# ESP32.net
KiCad netlist of a schematic drawn in Altium Designer
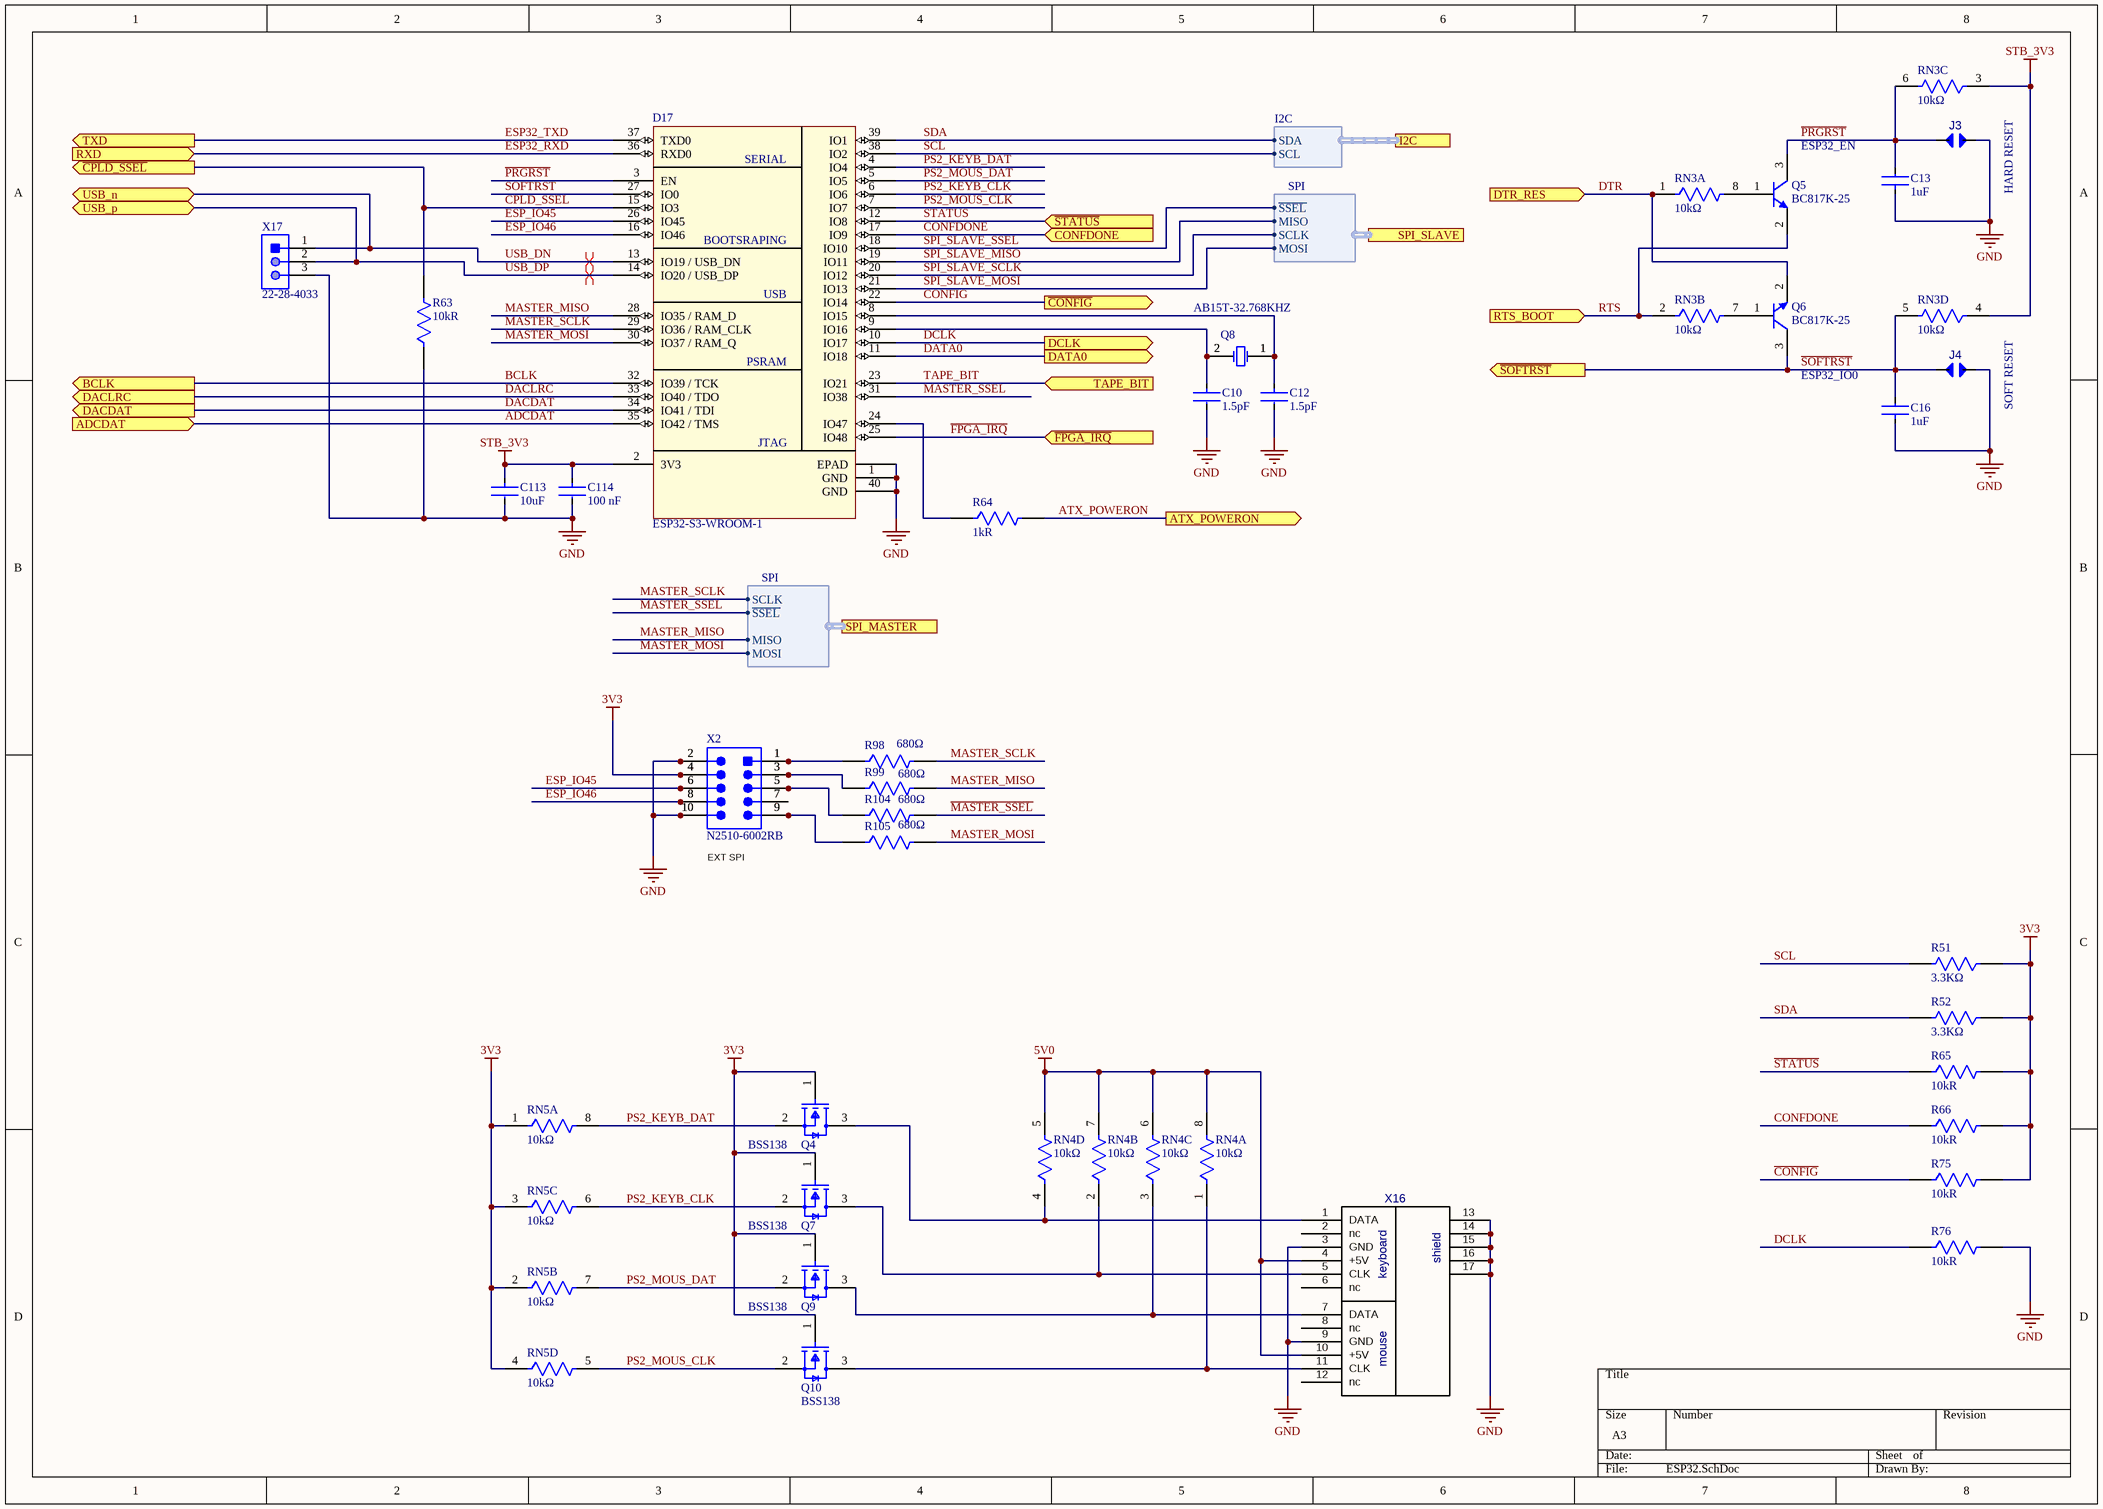
[diagram p0: ESP32.SchDoc]

(export (version "E")
  (design (tool "Eeschema 10.0.6"))
  (components
    (comp (ref "C10")
      (value "CL21C1R5CBANNNC")
      (footprint "FP-CL21-IPC_A")
      (description "CL21 Series 0805 1.5pF 50V ±0.25pF Tolerance C0G Multilayer Ceramic Chip Capacitor")
      (fields (field (name "CAPACITANCE") "1.5pF") (field (name "MANUFACTURER") "Samsung"))
      (libsource (lib "SchLib") (part "CMP-13271-001925-1"))
    )
    (comp (ref "C12")
      (value "CL21C1R5CBANNNC")
      (footprint "FP-CL21-IPC_A")
      (description "CL21 Series 0805 1.5pF 50V ±0.25pF Tolerance C0G Multilayer Ceramic Chip Capacitor")
      (fields (field (name "CAPACITANCE") "1.5pF") (field (name "MANUFACTURER") "Samsung"))
      (libsource (lib "SchLib") (part "CMP-13271-001925-1"))
    )
    (comp (ref "C13")
      (value "GCM21BR71E105KA56L")
      (footprint "FP-GCM21B-0_15-IPC_A")
      (description "Ceramic Capacitor for Automotive 1uF ±10% 25VDC X7R 0805 Embossed T/R")
      (fields (field (name "CAPACITANCE") "1uF") (field (name "MANUFACTURER") "Murata"))
      (libsource (lib "SchLib") (part "CMP-2007-03346-2"))
    )
    (comp (ref "C16")
      (value "GCM21BR71E105KA56L")
      (footprint "FP-GCM21B-0_15-IPC_A")
      (description "Ceramic Capacitor for Automotive 1uF ±10% 25VDC X7R 0805 Embossed T/R")
      (fields (field (name "CAPACITANCE") "1uF") (field (name "MANUFACTURER") "Murata"))
      (libsource (lib "SchLib") (part "CMP-2007-03346-2"))
    )
    (comp (ref "C113")
      (value "C0805C106K8PACTU")
      (footprint "FP-C0805C-DG-IPC_A")
      (description "CAP CER 10UF 10V X5R 0805")
      (fields (field (name "MANUFACTURER") "KEMET") (field (name "CAPACITANCE") "10uF"))
      (libsource (lib "SchLib") (part "CMP-2007-03243-2"))
    )
    (comp (ref "C114")
      (value "CC0805KRX7R9BB104")
      (footprint "FP-CC0805-0_85-IPC_A")
      (description "CAP CER 0.1UF 50V X7R 0805")
      (fields (field (name "MANUFACTURER") "Yageo") (field (name "CAPACITANCE") "100 nF"))
      (libsource (lib "SchLib") (part "CMP-2100-03606-3"))
    )
    (comp (ref "D17")
      (value "ESP32-S3-WROOM-1")
      (footprint "ESP32S3WROOM1")
      (libsource (lib "SchLib") (part "ESP32-S3-WROOM-1"))
    )
    (comp (ref "J3")
      (value "JUMPER")
      (footprint "JUMPER_JUMPER(Primary)")
      (description "HLT->~IP")
      (libsource (lib "SchLib") (part "JUMPER"))
    )
    (comp (ref "J4")
      (value "JUMPER")
      (footprint "JUMPER_JUMPER(Primary)")
      (description "HLT->~IP")
      (libsource (lib "SchLib") (part "JUMPER"))
    )
    (comp (ref "Q4")
      (value "BSS138")
      (footprint "FP-318-08-IPC_B")
      (description "MOSFET N-CH 50V 220MA SOT-23")
      (fields (field (name "MANUFACTURER") "ON Semiconductor / Fairchild"))
      (libsource (lib "SchLib") (part "CMP-07173-000101-1"))
    )
    (comp (ref "Q5")
      (value "BC817K-25")
      (footprint "INF-SOT23_N")
      (description "NPN Silicon AF Transistor, 45 V VCEO, 500 mA IC, SOT23, Reel, Green")
      (fields (field (name "MANUFACTURER") "Infineon"))
      (libsource (lib "SchLib") (part "CMP-1177-00027-1"))
    )
    (comp (ref "Q6")
      (value "BC817K-25")
      (footprint "INF-SOT23_N")
      (description "NPN Silicon AF Transistor, 45 V VCEO, 500 mA IC, SOT23, Reel, Green")
      (fields (field (name "MANUFACTURER") "Infineon"))
      (libsource (lib "SchLib") (part "CMP-1177-00027-1"))
    )
    (comp (ref "Q7")
      (value "BSS138")
      (footprint "FP-318-08-IPC_B")
      (description "MOSFET N-CH 50V 220MA SOT-23")
      (fields (field (name "MANUFACTURER") "ON Semiconductor / Fairchild"))
      (libsource (lib "SchLib") (part "CMP-07173-000101-1"))
    )
    (comp (ref "Q8")
      (value "AB15T-32.768KHZ")
      (footprint "ABRA-AB15T-2_V")
      (fields (field (name "MANUFACTURER") "Abracon"))
      (libsource (lib "SchLib") (part "CMP-1326-00001-1"))
    )
    (comp (ref "Q9")
      (value "BSS138")
      (footprint "FP-318-08-IPC_B")
      (description "MOSFET N-CH 50V 220MA SOT-23")
      (fields (field (name "MANUFACTURER") "ON Semiconductor / Fairchild"))
      (libsource (lib "SchLib") (part "CMP-07173-000101-1"))
    )
    (comp (ref "Q10")
      (value "BSS138")
      (footprint "FP-318-08-IPC_B")
      (description "MOSFET N-CH 50V 220MA SOT-23")
      (fields (field (name "MANUFACTURER") "ON Semiconductor / Fairchild"))
      (libsource (lib "SchLib") (part "CMP-07173-000101-1"))
    )
    (comp (ref "R51")
      (value "RT0805FRE073K3L")
      (footprint "FP-RT0805-IPC_A")
      (description "RES SMD 3.3K OHM 1% 1/8W 0805")
      (fields (field (name "MANUFACTURER") "Yageo") (field (name "RESISTANCE") "3.3KΩ"))
      (libsource (lib "SchLib") (part "CMP-03412-025935-1"))
    )
    (comp (ref "R52")
      (value "RT0805FRE073K3L")
      (footprint "FP-RT0805-IPC_A")
      (description "RES SMD 3.3K OHM 1% 1/8W 0805")
      (fields (field (name "MANUFACTURER") "Yageo") (field (name "RESISTANCE") "3.3KΩ"))
      (libsource (lib "SchLib") (part "CMP-03412-025935-1"))
    )
    (comp (ref "R63")
      (value "CR0805-JW-103ELF")
      (footprint "FP-CR0805-IPC_A")
      (description "Thick Film Chip Resistors 0805 10kΩ 0.125W 5% 200ppm/°C")
      (fields (field (name "RESISTANCE") "10kR") (field (name "MANUFACTURER") "Bourns"))
      (libsource (lib "SchLib") (part "CMP-07231-003873-1"))
    )
    (comp (ref "R64")
      (value "MCR10ERTJ102")
      (footprint "FP-MCR10-IPC_A")
      (description "Thick Film Chip Resistor, 0805, 1kΩ, 5%, 200ppm/°C, 0.125W, 150V")
      (fields (field (name "RESISTANCE") "1kR") (field (name "MANUFACTURER") "Rohm"))
      (libsource (lib "SchLib") (part "CMP-08839-004390-1"))
    )
    (comp (ref "R65")
      (value "CR0805-JW-103ELF")
      (footprint "FP-CR0805-IPC_A")
      (description "Thick Film Chip Resistors 0805 10kΩ 0.125W 5% 200ppm/°C")
      (fields (field (name "RESISTANCE") "10kR") (field (name "MANUFACTURER") "Bourns"))
      (libsource (lib "SchLib") (part "CMP-07231-003873-1"))
    )
    (comp (ref "R66")
      (value "CR0805-JW-103ELF")
      (footprint "FP-CR0805-IPC_A")
      (description "Thick Film Chip Resistors 0805 10kΩ 0.125W 5% 200ppm/°C")
      (fields (field (name "RESISTANCE") "10kR") (field (name "MANUFACTURER") "Bourns"))
      (libsource (lib "SchLib") (part "CMP-07231-003873-1"))
    )
    (comp (ref "R75")
      (value "CR0805-JW-103ELF")
      (footprint "FP-CR0805-IPC_A")
      (description "Thick Film Chip Resistors 0805 10kΩ 0.125W 5% 200ppm/°C")
      (fields (field (name "RESISTANCE") "10kR") (field (name "MANUFACTURER") "Bourns"))
      (libsource (lib "SchLib") (part "CMP-07231-003873-1"))
    )
    (comp (ref "R76")
      (value "CR0805-JW-103ELF")
      (footprint "FP-CR0805-IPC_A")
      (description "Thick Film Chip Resistors 0805 10kΩ 0.125W 5% 200ppm/°C")
      (fields (field (name "RESISTANCE") "10kR") (field (name "MANUFACTURER") "Bourns"))
      (libsource (lib "SchLib") (part "CMP-07231-003873-1"))
    )
    (comp (ref "R98")
      (value "680Ω")
      (footprint "FP-RT0805-IPC_A")
      (description "RES SMD 680 OHM 1% 1/8W 0805")
      (fields
        (field (name "MANUFACTURER") "Yageo")
        (field (name "MANUFACTURER PART NUMBER") "RT0805FRE07680RL")
      )
      (libsource (lib "SchLib") (part "CMP-03412-000082-1"))
    )
    (comp (ref "R99")
      (value "680Ω")
      (footprint "FP-RT0805-IPC_A")
      (description "RES SMD 680 OHM 1% 1/8W 0805")
      (fields
        (field (name "MANUFACTURER") "Yageo")
        (field (name "MANUFACTURER PART NUMBER") "RT0805FRE07680RL")
      )
      (libsource (lib "SchLib") (part "CMP-03412-000082-1"))
    )
    (comp (ref "R104")
      (value "680Ω")
      (footprint "FP-RT0805-IPC_A")
      (description "RES SMD 680 OHM 1% 1/8W 0805")
      (fields
        (field (name "MANUFACTURER") "Yageo")
        (field (name "MANUFACTURER PART NUMBER") "RT0805FRE07680RL")
      )
      (libsource (lib "SchLib") (part "CMP-03412-000082-1"))
    )
    (comp (ref "R105")
      (value "680Ω")
      (footprint "FP-RT0805-IPC_A")
      (description "RES SMD 680 OHM 1% 1/8W 0805")
      (fields
        (field (name "MANUFACTURER") "Yageo")
        (field (name "MANUFACTURER PART NUMBER") "RT0805FRE07680RL")
      )
      (libsource (lib "SchLib") (part "CMP-03412-000082-1"))
    )
    (comp (ref "RN3")
      (value "CAT16-1002F4LF")
      (footprint "FP-CAT16-F4-MFG")
      (description "RES ARRAY 4 RES 10K OHM 1206")
      (fields
        (field (name "RESISTANCE") "10kΩ")
        (field (name "TOLERANCE") "1%")
        (field (name "OCTOPART") "https://octopart.com/cat16-1002f4lf-bourns-1624551")
      )
      (libsource (lib "Altium Content Vault") (part "46c0e806a6f3a765a2d55930d12d044"))
    )
    (comp (ref "RN4")
      (value "CAT16-1002F4LF")
      (footprint "FP-CAT16-F4-MFG")
      (description "RES ARRAY 4 RES 10K OHM 1206")
      (fields
        (field (name "RESISTANCE") "10kΩ")
        (field (name "TOLERANCE") "1%")
        (field (name "OCTOPART") "https://octopart.com/cat16-1002f4lf-bourns-1624551")
      )
      (libsource (lib "Altium Content Vault") (part "46c0e806a6f3a765a2d55930d12d044"))
    )
    (comp (ref "RN5")
      (value "CAT16-1002F4LF")
      (footprint "FP-CAT16-F4-MFG")
      (description "RES ARRAY 4 RES 10K OHM 1206")
      (fields
        (field (name "RESISTANCE") "10kΩ")
        (field (name "TOLERANCE") "1%")
        (field (name "OCTOPART") "https://octopart.com/cat16-1002f4lf-bourns-1624551")
      )
      (libsource (lib "Altium Content Vault") (part "46c0e806a6f3a765a2d55930d12d044"))
    )
    (comp (ref "X2")
      (value "N2510-6002RB")
      (footprint "3M-N2510-6002-10_V")
      (fields (field (name "PARTNUMBER") "N2510") (field (name "MANUFACTURER") "3M"))
      (libsource (lib "SchLib") (part "CMP-2000-06794-1"))
    )
    (comp (ref "X16")
      (value "KEYB-MOUSE")
      (footprint "MDD-6FR")
      (libsource (lib "SchLib") (part "KEYB-MOUSE"))
    )
    (comp (ref "X17")
      (value "22-28-4033")
      (footprint "MOLX-22-28-4033_V")
      (description "Male Header, Pitch 2.54 mm, 1 x 3 Position, Height 8.38 mm, Tail Length 3.18 mm, RoHS, Bulk")
      (fields (field (name "MANUFACTURER") "Molex"))
      (libsource (lib "SchLib") (part "CMP-1676-00001-5"))
    )
  )
  (nets
    (net (code "3") (name "/ADCDAT") (class "Default")
      (node (ref "D17") (pin "35") (pinfunction "IO42_/_TMS_35") (pintype "bidirectional"))
    )
    (net (code "4") (name "/ATX_POWERON") (class "Default")
      (node (ref "R64") (pin "2") (pinfunction "2_2") (pintype "passive"))
    )
    (net (code "5") (name "/BCLK") (class "Default")
      (node (ref "D17") (pin "32") (pinfunction "IO39_/_TCK_32") (pintype "bidirectional"))
    )
    (net (code "6") (name "/CONFDONE") (class "Default")
      (node (ref "D17") (pin "17") (pinfunction "IO9_17") (pintype "bidirectional"))
      (node (ref "R66") (pin "1") (pinfunction "1_1") (pintype "passive"))
    )
    (net (code "7") (name "/DACDAT") (class "Default")
      (node (ref "D17") (pin "34") (pinfunction "IO41_/_TDI_34") (pintype "bidirectional"))
    )
    (net (code "8") (name "/DACLRC") (class "Default")
      (node (ref "D17") (pin "33") (pinfunction "IO40_/_TDO_33") (pintype "bidirectional"))
    )
    (net (code "9") (name "/DATA0") (class "Default")
      (node (ref "D17") (pin "11") (pinfunction "IO18_11") (pintype "bidirectional"))
    )
    (net (code "10") (name "/DCLK") (class "Default")
      (node (ref "D17") (pin "10") (pinfunction "IO17_10") (pintype "bidirectional"))
      (node (ref "R76") (pin "1") (pinfunction "1_1") (pintype "passive"))
    )
    (net (code "11") (name "/DTR") (class "Default")
      (node (ref "Q6") (pin "2") (pinfunction "E_2") (pintype "passive"))
      (node (ref "RN3") (pin "1") (pinfunction "1_1") (pintype "passive"))
    )
    (net (code "12") (name "/ESP32_RXD") (class "Default")
      (node (ref "D17") (pin "36") (pinfunction "RXD0_36") (pintype "bidirectional"))
    )
    (net (code "13") (name "/ESP32_TXD") (class "Default")
      (node (ref "D17") (pin "37") (pinfunction "TXD0_37") (pintype "bidirectional"))
    )
    (net (code "14") (name "/ESP_IO45") (class "Default")
      (node (ref "D17") (pin "26") (pinfunction "IO45_26") (pintype "bidirectional"))
      (node (ref "X2") (pin "6") (pinfunction "6_6") (pintype "passive"))
    )
    (net (code "15") (name "/ESP_IO46") (class "Default")
      (node (ref "D17") (pin "16") (pinfunction "IO46_16") (pintype "bidirectional"))
      (node (ref "X2") (pin "8") (pinfunction "8_8") (pintype "passive"))
    )
    (net (code "16") (name "/MASTER_MISO") (class "Default")
      (node (ref "D17") (pin "28") (pinfunction "IO35_/_RAM_D_28") (pintype "bidirectional"))
      (node (ref "R99") (pin "2") (pinfunction "2_2") (pintype "passive"))
    )
    (net (code "17") (name "/MASTER_MOSI") (class "Default")
      (node (ref "D17") (pin "30") (pinfunction "IO37_/_RAM_Q_30") (pintype "bidirectional"))
      (node (ref "R105") (pin "2") (pinfunction "2_2") (pintype "passive"))
    )
    (net (code "18") (name "/MASTER_SCLK") (class "Default")
      (node (ref "D17") (pin "29") (pinfunction "IO36_/_RAM_CLK_29") (pintype "bidirectional"))
      (node (ref "R98") (pin "2") (pinfunction "2_2") (pintype "passive"))
    )
    (net (code "19") (name "/PS2_KEYB_CLK") (class "Default")
      (node (ref "D17") (pin "6") (pinfunction "IO6_6") (pintype "bidirectional"))
      (node (ref "Q7") (pin "2") (pinfunction "S_2") (pintype "passive"))
      (node (ref "RN5") (pin "6") (pinfunction "6_6") (pintype "passive"))
    )
    (net (code "20") (name "/PS2_KEYB_DAT") (class "Default")
      (node (ref "D17") (pin "4") (pinfunction "IO4_4") (pintype "bidirectional"))
      (node (ref "Q4") (pin "2") (pinfunction "S_2") (pintype "passive"))
      (node (ref "RN5") (pin "8") (pinfunction "8_8") (pintype "passive"))
    )
    (net (code "21") (name "/PS2_MOUS_CLK") (class "Default")
      (node (ref "D17") (pin "7") (pinfunction "IO7_7") (pintype "bidirectional"))
      (node (ref "Q10") (pin "2") (pinfunction "S_2") (pintype "passive"))
      (node (ref "RN5") (pin "5") (pinfunction "5_5") (pintype "passive"))
    )
    (net (code "22") (name "/PS2_MOUS_DAT") (class "Default")
      (node (ref "D17") (pin "5") (pinfunction "IO5_5") (pintype "bidirectional"))
      (node (ref "Q9") (pin "2") (pinfunction "S_2") (pintype "passive"))
      (node (ref "RN5") (pin "7") (pinfunction "7_7") (pintype "passive"))
    )
    (net (code "23") (name "/RTS") (class "Default")
      (node (ref "Q5") (pin "2") (pinfunction "E_2") (pintype "passive"))
      (node (ref "RN3") (pin "2") (pinfunction "2_2") (pintype "passive"))
    )
    (net (code "24") (name "/SCL") (class "Default")
      (node (ref "D17") (pin "38") (pinfunction "IO2_38") (pintype "bidirectional"))
      (node (ref "R51") (pin "2") (pinfunction "2_2") (pintype "passive"))
    )
    (net (code "25") (name "/SDA") (class "Default")
      (node (ref "D17") (pin "39") (pinfunction "IO1_39") (pintype "bidirectional"))
      (node (ref "R52") (pin "2") (pinfunction "2_2") (pintype "passive"))
    )
    (net (code "26") (name "/SPI_SLAVE_MISO") (class "Default")
      (node (ref "D17") (pin "19") (pinfunction "IO11_19") (pintype "bidirectional"))
    )
    (net (code "27") (name "/SPI_SLAVE_MOSI") (class "Default")
      (node (ref "D17") (pin "21") (pinfunction "IO13_21") (pintype "bidirectional"))
    )
    (net (code "28") (name "/SPI_SLAVE_SCLK") (class "Default")
      (node (ref "D17") (pin "20") (pinfunction "IO12_20") (pintype "bidirectional"))
    )
    (net (code "29") (name "/TAPE_BIT") (class "Default")
      (node (ref "D17") (pin "23") (pinfunction "IO21_23") (pintype "bidirectional"))
    )
    (net (code "30") (name "/USB_DN") (class "Default")
      (node (ref "D17") (pin "13") (pinfunction "IO19_/_USB_DN_13") (pintype "bidirectional"))
      (node (ref "X17") (pin "1") (pinfunction "1_1") (pintype "passive"))
    )
    (net (code "31") (name "/USB_DP") (class "Default")
      (node (ref "D17") (pin "14") (pinfunction "IO20_/_USB_DP_14") (pintype "bidirectional"))
      (node (ref "X17") (pin "2") (pinfunction "2_2") (pintype "passive"))
    )
    (net (code "34") (name "/~{CONFIG}") (class "Default")
      (node (ref "D17") (pin "22") (pinfunction "IO14_22") (pintype "bidirectional"))
      (node (ref "R75") (pin "1") (pinfunction "1_1") (pintype "passive"))
    )
    (net (code "35") (name "/~{CPLD_SSEL}") (class "Default")
      (node (ref "D17") (pin "15") (pinfunction "IO3_15") (pintype "bidirectional"))
      (node (ref "R63") (pin "2") (pinfunction "2_2") (pintype "passive"))
    )
    (net (code "36") (name "/~{FPGA_IRQ}") (class "Default")
      (node (ref "D17") (pin "25") (pinfunction "IO48_25") (pintype "bidirectional"))
    )
    (net (code "37") (name "/~{MASTER_SSEL}") (class "Default")
      (node (ref "D17") (pin "31") (pinfunction "IO38_31") (pintype "bidirectional"))
      (node (ref "R104") (pin "2") (pinfunction "2_2") (pintype "passive"))
    )
    (net (code "38") (name "/~{PRGRST}") (class "Default")
      (node (ref "C13") (pin "2") (pinfunction "2_2") (pintype "passive"))
      (node (ref "D17") (pin "3") (pinfunction "EN_3") (pintype "power_in"))
      (node (ref "J3") (pin "0") (pinfunction "1_0") (pintype "passive"))
      (node (ref "Q5") (pin "3") (pinfunction "C_3") (pintype "passive"))
      (node (ref "RN3") (pin "6") (pinfunction "6_6") (pintype "passive"))
    )
    (net (code "39") (name "/~{SOFTRST}") (class "Default")
      (node (ref "C16") (pin "2") (pinfunction "2_2") (pintype "passive"))
      (node (ref "D17") (pin "27") (pinfunction "IO0_27") (pintype "bidirectional"))
      (node (ref "J4") (pin "0") (pinfunction "1_0") (pintype "passive"))
      (node (ref "Q6") (pin "3") (pinfunction "C_3") (pintype "passive"))
      (node (ref "RN3") (pin "5") (pinfunction "5_5") (pintype "passive"))
    )
    (net (code "40") (name "/~{SPI_SLAVE_SSEL}") (class "Default")
      (node (ref "D17") (pin "18") (pinfunction "IO10_18") (pintype "bidirectional"))
    )
    (net (code "41") (name "/~{STATUS}") (class "Default")
      (node (ref "D17") (pin "12") (pinfunction "IO8_12") (pintype "bidirectional"))
      (node (ref "R65") (pin "1") (pinfunction "1_1") (pintype "passive"))
    )
    (net (code "42") (name "3V3") (class "Default")
      (node (ref "Q10") (pin "1") (pinfunction "G_1") (pintype "passive"))
      (node (ref "Q4") (pin "1") (pinfunction "G_1") (pintype "passive"))
      (node (ref "Q7") (pin "1") (pinfunction "G_1") (pintype "passive"))
      (node (ref "Q9") (pin "1") (pinfunction "G_1") (pintype "passive"))
      (node (ref "R51") (pin "1") (pinfunction "1_1") (pintype "passive"))
      (node (ref "R52") (pin "1") (pinfunction "1_1") (pintype "passive"))
      (node (ref "R65") (pin "2") (pinfunction "2_2") (pintype "passive"))
      (node (ref "R66") (pin "2") (pinfunction "2_2") (pintype "passive"))
      (node (ref "R75") (pin "2") (pinfunction "2_2") (pintype "passive"))
      (node (ref "RN5") (pin "1") (pinfunction "1_1") (pintype "passive"))
      (node (ref "RN5") (pin "2") (pinfunction "2_2") (pintype "passive"))
      (node (ref "RN5") (pin "3") (pinfunction "3_3") (pintype "passive"))
      (node (ref "RN5") (pin "4") (pinfunction "4_4") (pintype "passive"))
      (node (ref "X2") (pin "4") (pinfunction "4_4") (pintype "passive"))
    )
    (net (code "43") (name "5V0") (class "Default")
      (node (ref "RN4") (pin "5") (pinfunction "5_5") (pintype "passive"))
      (node (ref "RN4") (pin "6") (pinfunction "6_6") (pintype "passive"))
      (node (ref "RN4") (pin "7") (pinfunction "7_7") (pintype "passive"))
      (node (ref "RN4") (pin "8") (pinfunction "8_8") (pintype "passive"))
      (node (ref "X16") (pin "10") (pinfunction "+5V_10") (pintype "passive"))
      (node (ref "X16") (pin "4") (pinfunction "+5V_4") (pintype "passive"))
    )
    (net (code "44") (name "GND") (class "Default")
      (node (ref "C10") (pin "2") (pinfunction "2_2") (pintype "passive"))
      (node (ref "C113") (pin "2") (pinfunction "2_2") (pintype "passive"))
      (node (ref "C114") (pin "2") (pinfunction "2_2") (pintype "passive"))
      (node (ref "C12") (pin "2") (pinfunction "2_2") (pintype "passive"))
      (node (ref "C13") (pin "1") (pinfunction "1_1") (pintype "passive"))
      (node (ref "C16") (pin "1") (pinfunction "1_1") (pintype "passive"))
      (node (ref "D17") (pin "1") (pinfunction "GND_1") (pintype "power_in"))
      (node (ref "D17") (pin "40") (pinfunction "GND_40") (pintype "power_in"))
      (node (ref "D17") (pin "EPAD") (pinfunction "EPAD_EPAD") (pintype "power_in"))
      (node (ref "J3") (pin "1") (pinfunction "2_1") (pintype "passive"))
      (node (ref "J4") (pin "1") (pinfunction "2_1") (pintype "passive"))
      (node (ref "R63") (pin "1") (pinfunction "1_1") (pintype "passive"))
      (node (ref "R76") (pin "2") (pinfunction "2_2") (pintype "passive"))
      (node (ref "X16") (pin "13") (pinfunction "shield_13") (pintype "passive"))
      (node (ref "X16") (pin "14") (pinfunction "shield_14") (pintype "passive"))
      (node (ref "X16") (pin "15") (pinfunction "shield_15") (pintype "passive"))
      (node (ref "X16") (pin "16") (pinfunction "shield_16") (pintype "passive"))
      (node (ref "X16") (pin "17") (pinfunction "shield_17") (pintype "passive"))
      (node (ref "X16") (pin "3") (pinfunction "GND_3") (pintype "passive"))
      (node (ref "X16") (pin "9") (pinfunction "GND_9") (pintype "passive"))
      (node (ref "X17") (pin "3") (pinfunction "3_3") (pintype "passive"))
      (node (ref "X2") (pin "10") (pinfunction "10_10") (pintype "passive"))
      (node (ref "X2") (pin "2") (pinfunction "2_2") (pintype "passive"))
    )
    (net (code "45") (name "Net-(D17-IO15)") (class "Default")
      (node (ref "C12") (pin "1") (pinfunction "1_1") (pintype "passive"))
      (node (ref "D17") (pin "8") (pinfunction "IO15_8") (pintype "bidirectional"))
      (node (ref "Q8") (pin "1") (pinfunction "X1_1") (pintype "passive"))
    )
    (net (code "46") (name "Net-(D17-IO16)") (class "Default")
      (node (ref "C10") (pin "1") (pinfunction "1_1") (pintype "passive"))
      (node (ref "D17") (pin "9") (pinfunction "IO16_9") (pintype "bidirectional"))
      (node (ref "Q8") (pin "2") (pinfunction "X2_2") (pintype "passive"))
    )
    (net (code "47") (name "Net-(D17-IO47)") (class "Default")
      (node (ref "D17") (pin "24") (pinfunction "IO47_24") (pintype "bidirectional"))
      (node (ref "R64") (pin "1") (pinfunction "1_1") (pintype "passive"))
    )
    (net (code "48") (name "Net-(Q4-D)") (class "Default")
      (node (ref "Q4") (pin "3") (pinfunction "D_3") (pintype "passive"))
      (node (ref "RN4") (pin "4") (pinfunction "4_4") (pintype "passive"))
      (node (ref "X16") (pin "1") (pinfunction "DATA_1") (pintype "passive"))
    )
    (net (code "49") (name "Net-(Q5-B)") (class "Default")
      (node (ref "Q5") (pin "1") (pinfunction "B_1") (pintype "passive"))
      (node (ref "RN3") (pin "8") (pinfunction "8_8") (pintype "passive"))
    )
    (net (code "50") (name "Net-(Q6-B)") (class "Default")
      (node (ref "Q6") (pin "1") (pinfunction "B_1") (pintype "passive"))
      (node (ref "RN3") (pin "7") (pinfunction "7_7") (pintype "passive"))
    )
    (net (code "51") (name "Net-(Q7-D)") (class "Default")
      (node (ref "Q7") (pin "3") (pinfunction "D_3") (pintype "passive"))
      (node (ref "RN4") (pin "2") (pinfunction "2_2") (pintype "passive"))
      (node (ref "X16") (pin "5") (pinfunction "CLK_5") (pintype "passive"))
    )
    (net (code "52") (name "Net-(Q9-D)") (class "Default")
      (node (ref "Q9") (pin "3") (pinfunction "D_3") (pintype "passive"))
      (node (ref "RN4") (pin "3") (pinfunction "3_3") (pintype "passive"))
      (node (ref "X16") (pin "7") (pinfunction "DATA_7") (pintype "passive"))
    )
    (net (code "53") (name "Net-(Q10-D)") (class "Default")
      (node (ref "Q10") (pin "3") (pinfunction "D_3") (pintype "passive"))
      (node (ref "RN4") (pin "1") (pinfunction "1_1") (pintype "passive"))
      (node (ref "X16") (pin "11") (pinfunction "CLK_11") (pintype "passive"))
    )
    (net (code "54") (name "Net-(R98-Pad1)") (class "Default")
      (node (ref "R98") (pin "1") (pinfunction "1_1") (pintype "passive"))
      (node (ref "X2") (pin "1") (pinfunction "1_1") (pintype "passive"))
    )
    (net (code "55") (name "Net-(R99-Pad1)") (class "Default")
      (node (ref "R99") (pin "1") (pinfunction "1_1") (pintype "passive"))
      (node (ref "X2") (pin "3") (pinfunction "3_3") (pintype "passive"))
    )
    (net (code "56") (name "Net-(R104-Pad1)") (class "Default")
      (node (ref "R104") (pin "1") (pinfunction "1_1") (pintype "passive"))
      (node (ref "X2") (pin "5") (pinfunction "5_5") (pintype "passive"))
    )
    (net (code "57") (name "Net-(R105-Pad1)") (class "Default")
      (node (ref "R105") (pin "1") (pinfunction "1_1") (pintype "passive"))
      (node (ref "X2") (pin "9") (pinfunction "9_9") (pintype "passive"))
    )
    (net (code "58") (name "Net-(X2-Pad7)") (class "Default")
      (node (ref "X2") (pin "7") (pinfunction "7_7") (pintype "passive"))
    )
    (net (code "59") (name "STB_3V3") (class "Default")
      (node (ref "C113") (pin "1") (pinfunction "1_1") (pintype "passive"))
      (node (ref "C114") (pin "1") (pinfunction "1_1") (pintype "passive"))
      (node (ref "D17") (pin "2") (pinfunction "3V3_2") (pintype "power_in"))
      (node (ref "RN3") (pin "3") (pinfunction "3_3") (pintype "passive"))
      (node (ref "RN3") (pin "4") (pinfunction "4_4") (pintype "passive"))
    )
    (net (code "60") (name "unconnected-(X16-nc-Pad2)") (class "Default")
      (node (ref "X16") (pin "2") (pinfunction "nc_2") (pintype "passive"))
    )
    (net (code "61") (name "unconnected-(X16-nc-Pad6)") (class "Default")
      (node (ref "X16") (pin "6") (pinfunction "nc_6") (pintype "passive"))
    )
    (net (code "62") (name "unconnected-(X16-nc-Pad8)") (class "Default")
      (node (ref "X16") (pin "8") (pinfunction "nc_8") (pintype "passive"))
    )
    (net (code "63") (name "unconnected-(X16-nc-Pad12)") (class "Default")
      (node (ref "X16") (pin "12") (pinfunction "nc_12") (pintype "passive"))
    )
  )
)
